# floppyswitch_4layer_smd.net
KiCad netlist of a schematic drawn in EAGLE
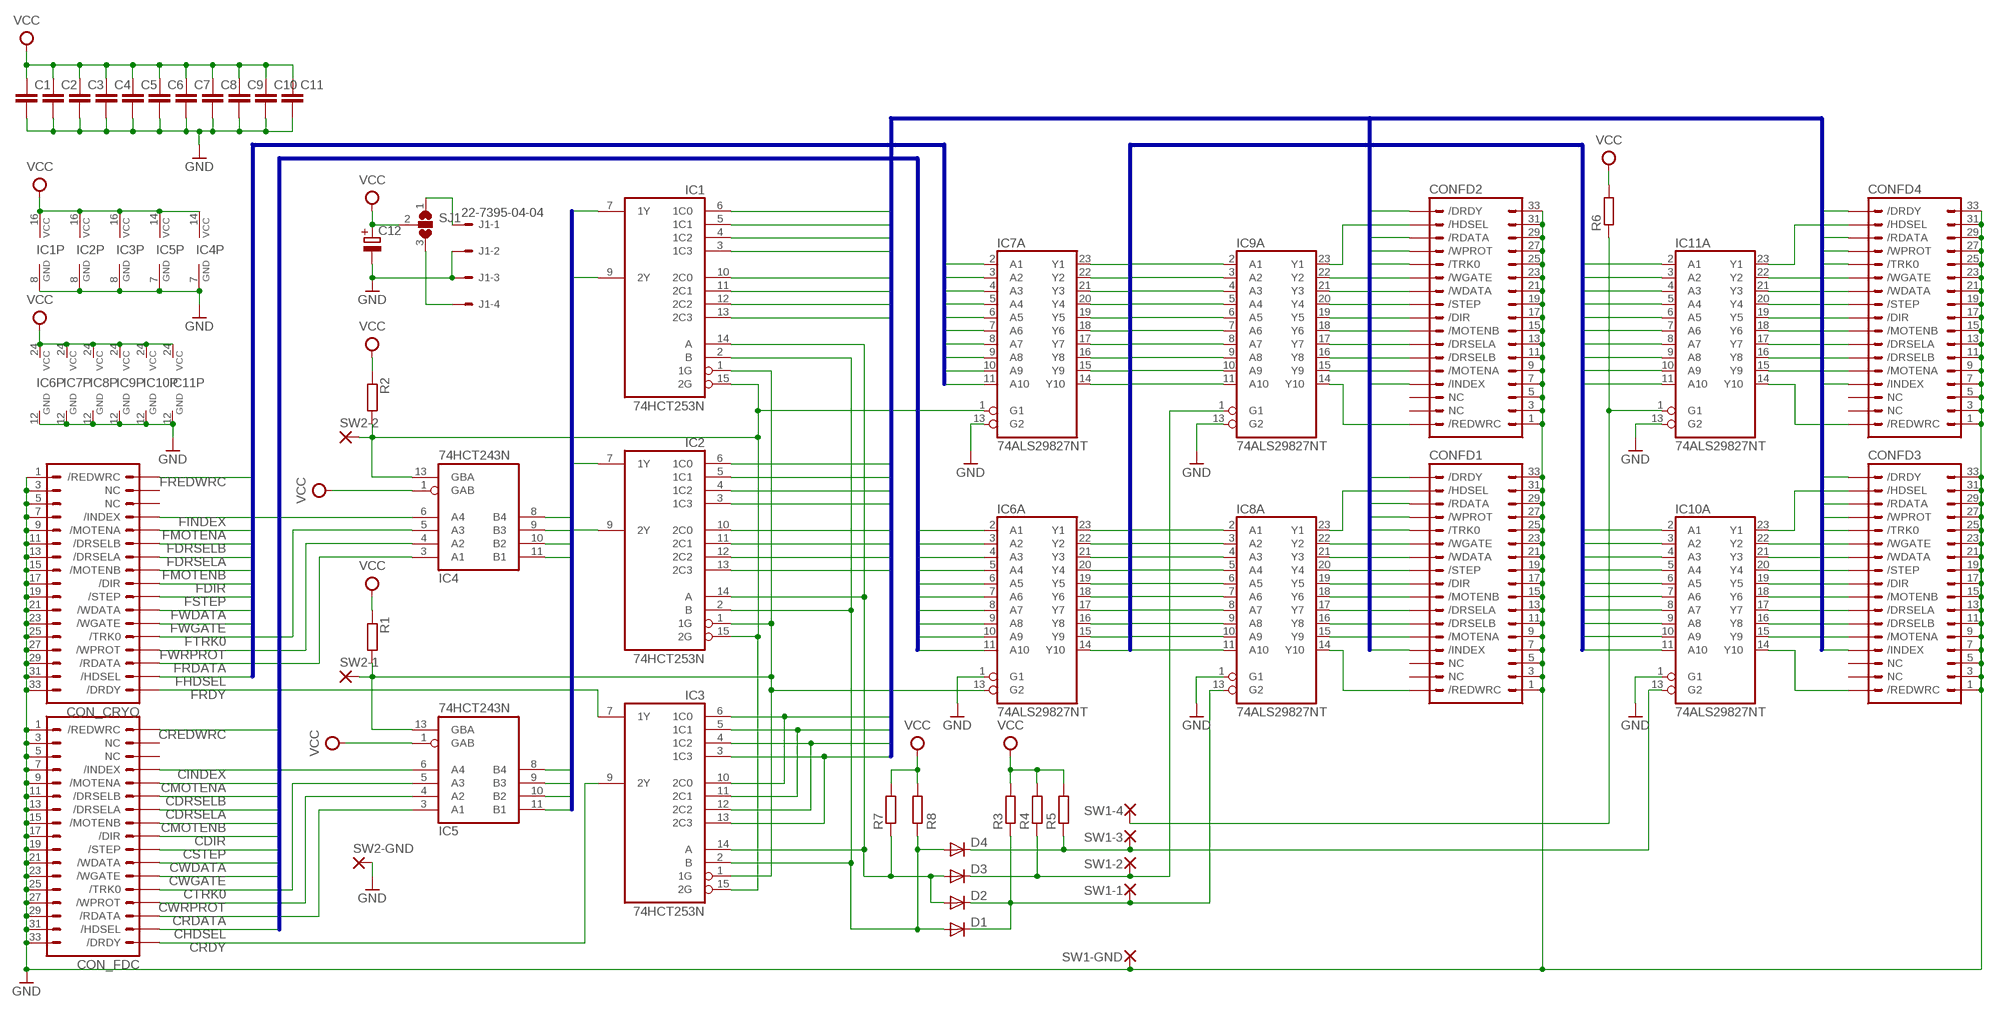
[diagram p0: schematic, sheet 1]

(export (version "E")
  (design (tool "Eeschema 10.0.6"))
  (components
    (comp (ref "C1")
      (value "C-EU075-032X103")
      (footprint "eagle-import:C075-032X103")
      (libsource (lib "eagle-import") (part "C-EU075-032X103"))
    )
    (comp (ref "C2")
      (value "C-EU025-025X050")
      (footprint "eagle-import:C025-025X050")
      (libsource (lib "eagle-import") (part "C-EU025-025X050"))
    )
    (comp (ref "C3")
      (value "C-EU050-025X075")
      (footprint "eagle-import:C050-025X075")
      (libsource (lib "eagle-import") (part "C-EU050-025X075"))
    )
    (comp (ref "C4")
      (value "C-EU050-025X075")
      (footprint "eagle-import:C050-025X075")
      (libsource (lib "eagle-import") (part "C-EU050-025X075"))
    )
    (comp (ref "C5")
      (value "C-EU075-032X103")
      (footprint "eagle-import:C075-032X103")
      (libsource (lib "eagle-import") (part "C-EU075-032X103"))
    )
    (comp (ref "C6")
      (value "C-EU075-032X103")
      (footprint "eagle-import:C075-032X103")
      (libsource (lib "eagle-import") (part "C-EU075-032X103"))
    )
    (comp (ref "C7")
      (value "C-EU075-032X103")
      (footprint "eagle-import:C075-032X103")
      (libsource (lib "eagle-import") (part "C-EU075-032X103"))
    )
    (comp (ref "C8")
      (value "C-EU075-032X103")
      (footprint "eagle-import:C075-032X103")
      (libsource (lib "eagle-import") (part "C-EU075-032X103"))
    )
    (comp (ref "C9")
      (value "C-EU075-032X103")
      (footprint "eagle-import:C075-032X103")
      (libsource (lib "eagle-import") (part "C-EU075-032X103"))
    )
    (comp (ref "C10")
      (value "C-EU075-032X103")
      (footprint "eagle-import:C075-032X103")
      (libsource (lib "eagle-import") (part "C-EU075-032X103"))
    )
    (comp (ref "C11")
      (value "C-EU050-025X075")
      (footprint "eagle-import:C050-025X075")
      (libsource (lib "eagle-import") (part "C-EU050-025X075"))
    )
    (comp (ref "C12")
      (value "CPOL-EUE2.5-6")
      (footprint "eagle-import:E2,5-6")
      (libsource (lib "eagle-import") (part "CPOL-EUE2.5-6"))
    )
    (comp (ref "CONFD1")
      (value "FDC342X17")
      (footprint "eagle-import:2X17")
      (libsource (lib "eagle-import") (part "FDC342X17"))
    )
    (comp (ref "CONFD2")
      (value "FDC342X17")
      (footprint "eagle-import:2X17")
      (libsource (lib "eagle-import") (part "FDC342X17"))
    )
    (comp (ref "CONFD3")
      (value "FDC342X17")
      (footprint "eagle-import:2X17")
      (libsource (lib "eagle-import") (part "FDC342X17"))
    )
    (comp (ref "CONFD4")
      (value "FDC342X17")
      (footprint "eagle-import:2X17")
      (libsource (lib "eagle-import") (part "FDC342X17"))
    )
    (comp (ref "CON_CRYO")
      (value "FDC342X17")
      (footprint "eagle-import:2X17")
      (libsource (lib "eagle-import") (part "FDC342X17"))
    )
    (comp (ref "CON_FDC")
      (value "FDC342X17")
      (footprint "eagle-import:2X17")
      (libsource (lib "eagle-import") (part "FDC342X17"))
    )
    (comp (ref "D1")
      (value "1N4148-7")
      (footprint "eagle-import:DO35-7")
      (libsource (lib "eagle-import") (part "1N4148-7"))
    )
    (comp (ref "D2")
      (value "1N4148-7")
      (footprint "eagle-import:DO35-7")
      (libsource (lib "eagle-import") (part "1N4148-7"))
    )
    (comp (ref "D3")
      (value "1N4148-7")
      (footprint "eagle-import:DO35-7")
      (libsource (lib "eagle-import") (part "1N4148-7"))
    )
    (comp (ref "D4")
      (value "1N4148-7")
      (footprint "eagle-import:DO35-7")
      (libsource (lib "eagle-import") (part "1N4148-7"))
    )
    (comp (ref "IC1")
      (value "74HCT253N")
      (footprint "eagle-import:DIL16")
      (libsource (lib "eagle-import") (part "74253NHCT"))
    )
    (comp (ref "IC2")
      (value "74HCT253N")
      (footprint "eagle-import:DIL16")
      (libsource (lib "eagle-import") (part "74253NHCT"))
    )
    (comp (ref "IC3")
      (value "74HCT253N")
      (footprint "eagle-import:DIL16")
      (libsource (lib "eagle-import") (part "74253NHCT"))
    )
    (comp (ref "IC4")
      (value "74HCT243N")
      (footprint "eagle-import:DIL14")
      (libsource (lib "eagle-import") (part "74243NHCT"))
    )
    (comp (ref "IC5")
      (value "74HCT243N")
      (footprint "eagle-import:DIL14")
      (libsource (lib "eagle-import") (part "74243NHCT"))
    )
    (comp (ref "IC6")
      (value "74ALS29827NT")
      (footprint "eagle-import:SO24W")
      (libsource (lib "eagle-import") (part "7429827NTALS"))
    )
    (comp (ref "IC7")
      (value "74ALS29827NT")
      (footprint "eagle-import:SO24W")
      (libsource (lib "eagle-import") (part "7429827NTALS"))
    )
    (comp (ref "IC8")
      (value "74ALS29827NT")
      (footprint "eagle-import:SO24W")
      (libsource (lib "eagle-import") (part "7429827NTALS"))
    )
    (comp (ref "IC9")
      (value "74ALS29827NT")
      (footprint "eagle-import:SO24W")
      (libsource (lib "eagle-import") (part "7429827NTALS"))
    )
    (comp (ref "IC10")
      (value "74ALS29827NT")
      (footprint "eagle-import:SO24W")
      (libsource (lib "eagle-import") (part "7429827NTALS"))
    )
    (comp (ref "IC11")
      (value "74ALS29827NT")
      (footprint "eagle-import:SO24W")
      (libsource (lib "eagle-import") (part "7429827NTALS"))
    )
    (comp (ref "J1")
      (value "22-7395-04-04")
      (footprint "eagle-import:7395-04")
      (libsource (lib "eagle-import") (part "22-?-047395-04"))
    )
    (comp (ref "R1")
      (value "R-EU0207/10")
      (footprint "eagle-import:0207_10")
      (libsource (lib "eagle-import") (part "R-EU0207/10"))
    )
    (comp (ref "R2")
      (value "R-EU0207/10")
      (footprint "eagle-import:0207_10")
      (libsource (lib "eagle-import") (part "R-EU0207/10"))
    )
    (comp (ref "R3")
      (value "R-EU0207/10")
      (footprint "eagle-import:0207_10")
      (libsource (lib "eagle-import") (part "R-EU0207/10"))
    )
    (comp (ref "R4")
      (value "R-EU0207/10")
      (footprint "eagle-import:0207_10")
      (libsource (lib "eagle-import") (part "R-EU0207/10"))
    )
    (comp (ref "R5")
      (value "R-EU0207/10")
      (footprint "eagle-import:0207_10")
      (libsource (lib "eagle-import") (part "R-EU0207/10"))
    )
    (comp (ref "R6")
      (value "R-EU0207/10")
      (footprint "eagle-import:0207_10")
      (libsource (lib "eagle-import") (part "R-EU0207/10"))
    )
    (comp (ref "R7")
      (value "R-EU0207/10")
      (footprint "eagle-import:0207_10")
      (libsource (lib "eagle-import") (part "R-EU0207/10"))
    )
    (comp (ref "R8")
      (value "R-EU0207/10")
      (footprint "eagle-import:0207_10")
      (libsource (lib "eagle-import") (part "R-EU0207/10"))
    )
    (comp (ref "SJ1")
      (value "SJ2W")
      (footprint "eagle-import:SJ_2")
      (libsource (lib "eagle-import") (part "SJ2W"))
    )
    (comp (ref "SW1-1")
      (value "WIREPAD1,6/0,8")
      (footprint "eagle-import:1,6_0,8")
      (libsource (lib "eagle-import") (part "WIREPAD1,6/0,8"))
    )
    (comp (ref "SW1-2")
      (value "WIREPAD1,6/0,8")
      (footprint "eagle-import:1,6_0,8")
      (libsource (lib "eagle-import") (part "WIREPAD1,6/0,8"))
    )
    (comp (ref "SW1-3")
      (value "WIREPAD1,6/0,8")
      (footprint "eagle-import:1,6_0,8")
      (libsource (lib "eagle-import") (part "WIREPAD1,6/0,8"))
    )
    (comp (ref "SW1-4")
      (value "WIREPAD1,6/0,8")
      (footprint "eagle-import:1,6_0,8")
      (libsource (lib "eagle-import") (part "WIREPAD1,6/0,8"))
    )
    (comp (ref "SW1-GND")
      (value "WIREPAD1,6/0,8")
      (footprint "eagle-import:1,6_0,8")
      (libsource (lib "eagle-import") (part "WIREPAD1,6/0,8"))
    )
    (comp (ref "SW2-1")
      (value "WIREPAD1,6/0,8")
      (footprint "eagle-import:1,6_0,8")
      (libsource (lib "eagle-import") (part "WIREPAD1,6/0,8"))
    )
    (comp (ref "SW2-2")
      (value "WIREPAD1,6/0,8")
      (footprint "eagle-import:1,6_0,8")
      (libsource (lib "eagle-import") (part "WIREPAD1,6/0,8"))
    )
    (comp (ref "SW2-GND")
      (value "WIREPAD1,6/0,8")
      (footprint "eagle-import:1,6_0,8")
      (libsource (lib "eagle-import") (part "WIREPAD1,6/0,8"))
    )
  )
  (nets
    (net (code "1") (name "/BUS1") (class "Default")
      (node (ref "IC10") (pin "11") (pinfunction "A10_11") (pintype "input"))
      (node (ref "IC11") (pin "11") (pinfunction "A10_11") (pintype "input"))
      (node (ref "IC6") (pin "14") (pinfunction "Y10_14") (pintype "tri_state"))
      (node (ref "IC7") (pin "14") (pinfunction "Y10_14") (pintype "tri_state"))
      (node (ref "IC8") (pin "11") (pinfunction "A10_11") (pintype "input"))
      (node (ref "IC9") (pin "11") (pinfunction "A10_11") (pintype "input"))
    )
    (net (code "2") (name "/BUS2") (class "Default")
      (node (ref "IC10") (pin "10") (pinfunction "A9_10") (pintype "input"))
      (node (ref "IC11") (pin "10") (pinfunction "A9_10") (pintype "input"))
      (node (ref "IC6") (pin "15") (pinfunction "Y9_15") (pintype "tri_state"))
      (node (ref "IC7") (pin "15") (pinfunction "Y9_15") (pintype "tri_state"))
      (node (ref "IC8") (pin "10") (pinfunction "A9_10") (pintype "input"))
      (node (ref "IC9") (pin "10") (pinfunction "A9_10") (pintype "input"))
    )
    (net (code "3") (name "/BUS3") (class "Default")
      (node (ref "IC10") (pin "9") (pinfunction "A8_9") (pintype "input"))
      (node (ref "IC11") (pin "9") (pinfunction "A8_9") (pintype "input"))
      (node (ref "IC6") (pin "16") (pinfunction "Y8_16") (pintype "tri_state"))
      (node (ref "IC7") (pin "16") (pinfunction "Y8_16") (pintype "tri_state"))
      (node (ref "IC8") (pin "9") (pinfunction "A8_9") (pintype "input"))
      (node (ref "IC9") (pin "9") (pinfunction "A8_9") (pintype "input"))
    )
    (net (code "4") (name "/BUS4") (class "Default")
      (node (ref "IC10") (pin "8") (pinfunction "A7_8") (pintype "input"))
      (node (ref "IC11") (pin "8") (pinfunction "A7_8") (pintype "input"))
      (node (ref "IC6") (pin "17") (pinfunction "Y7_17") (pintype "tri_state"))
      (node (ref "IC7") (pin "17") (pinfunction "Y7_17") (pintype "tri_state"))
      (node (ref "IC8") (pin "8") (pinfunction "A7_8") (pintype "input"))
      (node (ref "IC9") (pin "8") (pinfunction "A7_8") (pintype "input"))
    )
    (net (code "5") (name "/BUS5") (class "Default")
      (node (ref "IC10") (pin "7") (pinfunction "A6_7") (pintype "input"))
      (node (ref "IC11") (pin "7") (pinfunction "A6_7") (pintype "input"))
      (node (ref "IC6") (pin "18") (pinfunction "Y6_18") (pintype "tri_state"))
      (node (ref "IC7") (pin "18") (pinfunction "Y6_18") (pintype "tri_state"))
      (node (ref "IC8") (pin "7") (pinfunction "A6_7") (pintype "input"))
      (node (ref "IC9") (pin "7") (pinfunction "A6_7") (pintype "input"))
    )
    (net (code "6") (name "/BUS6") (class "Default")
      (node (ref "IC10") (pin "6") (pinfunction "A5_6") (pintype "input"))
      (node (ref "IC11") (pin "6") (pinfunction "A5_6") (pintype "input"))
      (node (ref "IC6") (pin "19") (pinfunction "Y5_19") (pintype "tri_state"))
      (node (ref "IC7") (pin "19") (pinfunction "Y5_19") (pintype "tri_state"))
      (node (ref "IC8") (pin "6") (pinfunction "A5_6") (pintype "input"))
      (node (ref "IC9") (pin "6") (pinfunction "A5_6") (pintype "input"))
    )
    (net (code "7") (name "/BUS7") (class "Default")
      (node (ref "IC10") (pin "5") (pinfunction "A4_5") (pintype "input"))
      (node (ref "IC11") (pin "5") (pinfunction "A4_5") (pintype "input"))
      (node (ref "IC6") (pin "20") (pinfunction "Y4_20") (pintype "tri_state"))
      (node (ref "IC7") (pin "20") (pinfunction "Y4_20") (pintype "tri_state"))
      (node (ref "IC8") (pin "5") (pinfunction "A4_5") (pintype "input"))
      (node (ref "IC9") (pin "5") (pinfunction "A4_5") (pintype "input"))
    )
    (net (code "8") (name "/BUS8") (class "Default")
      (node (ref "IC10") (pin "4") (pinfunction "A3_4") (pintype "input"))
      (node (ref "IC11") (pin "4") (pinfunction "A3_4") (pintype "input"))
      (node (ref "IC6") (pin "21") (pinfunction "Y3_21") (pintype "tri_state"))
      (node (ref "IC7") (pin "21") (pinfunction "Y3_21") (pintype "tri_state"))
      (node (ref "IC8") (pin "4") (pinfunction "A3_4") (pintype "input"))
      (node (ref "IC9") (pin "4") (pinfunction "A3_4") (pintype "input"))
    )
    (net (code "9") (name "/BUS9") (class "Default")
      (node (ref "IC10") (pin "3") (pinfunction "A2_3") (pintype "input"))
      (node (ref "IC11") (pin "3") (pinfunction "A2_3") (pintype "input"))
      (node (ref "IC6") (pin "22") (pinfunction "Y2_22") (pintype "tri_state"))
      (node (ref "IC7") (pin "22") (pinfunction "Y2_22") (pintype "tri_state"))
      (node (ref "IC8") (pin "3") (pinfunction "A2_3") (pintype "input"))
      (node (ref "IC9") (pin "3") (pinfunction "A2_3") (pintype "input"))
    )
    (net (code "10") (name "/BUS10") (class "Default")
      (node (ref "IC10") (pin "2") (pinfunction "A1_2") (pintype "input"))
      (node (ref "IC11") (pin "2") (pinfunction "A1_2") (pintype "input"))
      (node (ref "IC6") (pin "23") (pinfunction "Y1_23") (pintype "tri_state"))
      (node (ref "IC7") (pin "23") (pinfunction "Y1_23") (pintype "tri_state"))
      (node (ref "IC8") (pin "2") (pinfunction "A1_2") (pintype "input"))
      (node (ref "IC9") (pin "2") (pinfunction "A1_2") (pintype "input"))
    )
    (net (code "11") (name "/CDIR") (class "Default")
      (node (ref "CON_FDC") (pin "18") (pinfunction "/DIR_18") (pintype "output"))
      (node (ref "IC6") (pin "6") (pinfunction "A5_6") (pintype "input"))
    )
    (net (code "12") (name "/CDRSELA") (class "Default")
      (node (ref "CON_FDC") (pin "14") (pinfunction "/DRSELA_14") (pintype "output"))
      (node (ref "IC6") (pin "8") (pinfunction "A7_8") (pintype "input"))
    )
    (net (code "13") (name "/CDRSELB") (class "Default")
      (node (ref "CON_FDC") (pin "12") (pinfunction "/DRSELB_12") (pintype "output"))
      (node (ref "IC6") (pin "9") (pinfunction "A8_9") (pintype "input"))
    )
    (net (code "14") (name "/CHDSEL") (class "Default")
      (node (ref "CON_FDC") (pin "32") (pinfunction "/HDSEL_32") (pintype "output"))
      (node (ref "IC6") (pin "2") (pinfunction "A1_2") (pintype "input"))
    )
    (net (code "15") (name "/CINDEX") (class "Default")
      (node (ref "CON_FDC") (pin "8") (pinfunction "/INDEX_8") (pintype "input"))
      (node (ref "IC5") (pin "6") (pinfunction "A4_6") (pintype "bidirectional"))
    )
    (net (code "16") (name "/CMOTENA") (class "Default")
      (node (ref "CON_FDC") (pin "10") (pinfunction "/MOTENA_10") (pintype "output"))
      (node (ref "IC6") (pin "10") (pinfunction "A9_10") (pintype "input"))
    )
    (net (code "17") (name "/CMOTENB") (class "Default")
      (node (ref "CON_FDC") (pin "16") (pinfunction "/MOTENB_16") (pintype "output"))
      (node (ref "IC6") (pin "7") (pinfunction "A6_7") (pintype "input"))
    )
    (net (code "18") (name "/CRDATA") (class "Default")
      (node (ref "CON_FDC") (pin "30") (pinfunction "/RDATA_30") (pintype "input"))
      (node (ref "IC5") (pin "3") (pinfunction "A1_3") (pintype "bidirectional"))
    )
    (net (code "19") (name "/CRDY") (class "Default")
      (node (ref "CON_FDC") (pin "34") (pinfunction "/DRDY_34") (pintype "input"))
      (node (ref "IC3") (pin "9") (pinfunction "2Y_9") (pintype "tri_state"))
    )
    (net (code "20") (name "/CREDWRC") (class "Default")
      (node (ref "CON_FDC") (pin "2") (pinfunction "/REDWRC_2") (pintype "output"))
      (node (ref "IC6") (pin "11") (pinfunction "A10_11") (pintype "input"))
    )
    (net (code "21") (name "/CSTEP") (class "Default")
      (node (ref "CON_FDC") (pin "20") (pinfunction "/STEP_20") (pintype "output"))
      (node (ref "IC6") (pin "5") (pinfunction "A4_5") (pintype "input"))
    )
    (net (code "22") (name "/CTRK0") (class "Default")
      (node (ref "CON_FDC") (pin "26") (pinfunction "/TRK0_26") (pintype "input"))
      (node (ref "IC5") (pin "5") (pinfunction "A3_5") (pintype "bidirectional"))
    )
    (net (code "23") (name "/CWDATA") (class "Default")
      (node (ref "CON_FDC") (pin "22") (pinfunction "/WDATA_22") (pintype "output"))
      (node (ref "IC6") (pin "4") (pinfunction "A3_4") (pintype "input"))
    )
    (net (code "24") (name "/CWGATE") (class "Default")
      (node (ref "CON_FDC") (pin "24") (pinfunction "/WGATE_24") (pintype "output"))
      (node (ref "IC6") (pin "3") (pinfunction "A2_3") (pintype "input"))
    )
    (net (code "25") (name "/CWRPROT") (class "Default")
      (node (ref "CON_FDC") (pin "28") (pinfunction "/WPROT_28") (pintype "input"))
      (node (ref "IC5") (pin "4") (pinfunction "A2_4") (pintype "bidirectional"))
    )
    (net (code "26") (name "/FDIR") (class "Default")
      (node (ref "CON_CRYO") (pin "18") (pinfunction "/DIR_18") (pintype "output"))
      (node (ref "IC7") (pin "6") (pinfunction "A5_6") (pintype "input"))
    )
    (net (code "27") (name "/FDRSELA") (class "Default")
      (node (ref "CON_CRYO") (pin "14") (pinfunction "/DRSELA_14") (pintype "output"))
      (node (ref "IC7") (pin "8") (pinfunction "A7_8") (pintype "input"))
    )
    (net (code "28") (name "/FDRSELB") (class "Default")
      (node (ref "CON_CRYO") (pin "12") (pinfunction "/DRSELB_12") (pintype "output"))
      (node (ref "IC7") (pin "9") (pinfunction "A8_9") (pintype "input"))
    )
    (net (code "29") (name "/FHDSEL") (class "Default")
      (node (ref "CON_CRYO") (pin "32") (pinfunction "/HDSEL_32") (pintype "output"))
      (node (ref "IC7") (pin "2") (pinfunction "A1_2") (pintype "input"))
    )
    (net (code "30") (name "/FINDEX") (class "Default")
      (node (ref "CON_CRYO") (pin "8") (pinfunction "/INDEX_8") (pintype "input"))
      (node (ref "IC4") (pin "6") (pinfunction "A4_6") (pintype "bidirectional"))
    )
    (net (code "31") (name "/FMOTENA") (class "Default")
      (node (ref "CON_CRYO") (pin "10") (pinfunction "/MOTENA_10") (pintype "output"))
      (node (ref "IC7") (pin "10") (pinfunction "A9_10") (pintype "input"))
    )
    (net (code "32") (name "/FMOTENB") (class "Default")
      (node (ref "CON_CRYO") (pin "16") (pinfunction "/MOTENB_16") (pintype "output"))
      (node (ref "IC7") (pin "7") (pinfunction "A6_7") (pintype "input"))
    )
    (net (code "33") (name "/FRDATA") (class "Default")
      (node (ref "CON_CRYO") (pin "30") (pinfunction "/RDATA_30") (pintype "input"))
      (node (ref "IC4") (pin "3") (pinfunction "A1_3") (pintype "bidirectional"))
    )
    (net (code "34") (name "/FRDY") (class "Default")
      (node (ref "CON_CRYO") (pin "34") (pinfunction "/DRDY_34") (pintype "input"))
      (node (ref "IC3") (pin "7") (pinfunction "1Y_7") (pintype "tri_state"))
    )
    (net (code "35") (name "/FREDWRC") (class "Default")
      (node (ref "CON_CRYO") (pin "2") (pinfunction "/REDWRC_2") (pintype "output"))
      (node (ref "IC7") (pin "11") (pinfunction "A10_11") (pintype "input"))
    )
    (net (code "36") (name "/FSTEP") (class "Default")
      (node (ref "CON_CRYO") (pin "20") (pinfunction "/STEP_20") (pintype "output"))
      (node (ref "IC7") (pin "5") (pinfunction "A4_5") (pintype "input"))
    )
    (net (code "37") (name "/FTRK0") (class "Default")
      (node (ref "CON_CRYO") (pin "26") (pinfunction "/TRK0_26") (pintype "input"))
      (node (ref "IC4") (pin "5") (pinfunction "A3_5") (pintype "bidirectional"))
    )
    (net (code "38") (name "/FWDATA") (class "Default")
      (node (ref "CON_CRYO") (pin "22") (pinfunction "/WDATA_22") (pintype "output"))
      (node (ref "IC7") (pin "4") (pinfunction "A3_4") (pintype "input"))
    )
    (net (code "39") (name "/FWGATE") (class "Default")
      (node (ref "CON_CRYO") (pin "24") (pinfunction "/WGATE_24") (pintype "output"))
      (node (ref "IC7") (pin "3") (pinfunction "A2_3") (pintype "input"))
    )
    (net (code "40") (name "/FWRPROT") (class "Default")
      (node (ref "CON_CRYO") (pin "28") (pinfunction "/WPROT_28") (pintype "input"))
      (node (ref "IC4") (pin "4") (pinfunction "A2_4") (pintype "bidirectional"))
    )
    (net (code "41") (name "/INDEX") (class "Default")
      (node (ref "IC1") (pin "7") (pinfunction "1Y_7") (pintype "tri_state"))
      (node (ref "IC4") (pin "8") (pinfunction "B4_8") (pintype "bidirectional"))
      (node (ref "IC5") (pin "8") (pinfunction "B4_8") (pintype "bidirectional"))
    )
    (net (code "42") (name "/INDEX1") (class "Default")
      (node (ref "CONFD1") (pin "8") (pinfunction "/INDEX_8") (pintype "input"))
      (node (ref "IC1") (pin "6") (pinfunction "1C0_6") (pintype "input"))
    )
    (net (code "43") (name "/INDEX2") (class "Default")
      (node (ref "CONFD2") (pin "8") (pinfunction "/INDEX_8") (pintype "input"))
      (node (ref "IC1") (pin "5") (pinfunction "1C1_5") (pintype "input"))
    )
    (net (code "44") (name "/INDEX3") (class "Default")
      (node (ref "CONFD3") (pin "8") (pinfunction "/INDEX_8") (pintype "input"))
      (node (ref "IC1") (pin "4") (pinfunction "1C2_4") (pintype "input"))
    )
    (net (code "45") (name "/INDEX4") (class "Default")
      (node (ref "CONFD4") (pin "8") (pinfunction "/INDEX_8") (pintype "input"))
      (node (ref "IC1") (pin "3") (pinfunction "1C3_3") (pintype "input"))
    )
    (net (code "46") (name "/RDATA") (class "Default")
      (node (ref "IC2") (pin "9") (pinfunction "2Y_9") (pintype "tri_state"))
      (node (ref "IC4") (pin "11") (pinfunction "B1_11") (pintype "bidirectional"))
      (node (ref "IC5") (pin "11") (pinfunction "B1_11") (pintype "bidirectional"))
    )
    (net (code "47") (name "/RDATA1") (class "Default")
      (node (ref "CONFD1") (pin "30") (pinfunction "/RDATA_30") (pintype "input"))
      (node (ref "IC2") (pin "10") (pinfunction "2C0_10") (pintype "input"))
    )
    (net (code "48") (name "/RDATA2") (class "Default")
      (node (ref "CONFD2") (pin "30") (pinfunction "/RDATA_30") (pintype "input"))
      (node (ref "IC2") (pin "11") (pinfunction "2C1_11") (pintype "input"))
    )
    (net (code "49") (name "/RDATA3") (class "Default")
      (node (ref "CONFD3") (pin "30") (pinfunction "/RDATA_30") (pintype "input"))
      (node (ref "IC2") (pin "12") (pinfunction "2C2_12") (pintype "input"))
    )
    (net (code "50") (name "/RDATA4") (class "Default")
      (node (ref "CONFD4") (pin "30") (pinfunction "/RDATA_30") (pintype "input"))
      (node (ref "IC2") (pin "13") (pinfunction "2C3_13") (pintype "input"))
    )
    (net (code "51") (name "/RDY1") (class "Default")
      (node (ref "CONFD1") (pin "34") (pinfunction "/DRDY_34") (pintype "input"))
      (node (ref "IC3") (pin "10") (pinfunction "2C0_10") (pintype "input"))
      (node (ref "IC3") (pin "6") (pinfunction "1C0_6") (pintype "input"))
    )
    (net (code "52") (name "/RDY2") (class "Default")
      (node (ref "CONFD2") (pin "34") (pinfunction "/DRDY_34") (pintype "input"))
      (node (ref "IC3") (pin "11") (pinfunction "2C1_11") (pintype "input"))
      (node (ref "IC3") (pin "5") (pinfunction "1C1_5") (pintype "input"))
    )
    (net (code "53") (name "/RDY3") (class "Default")
      (node (ref "CONFD3") (pin "34") (pinfunction "/DRDY_34") (pintype "input"))
      (node (ref "IC3") (pin "12") (pinfunction "2C2_12") (pintype "input"))
      (node (ref "IC3") (pin "4") (pinfunction "1C2_4") (pintype "input"))
    )
    (net (code "54") (name "/RDY4") (class "Default")
      (node (ref "CONFD4") (pin "34") (pinfunction "/DRDY_34") (pintype "input"))
      (node (ref "IC3") (pin "13") (pinfunction "2C3_13") (pintype "input"))
      (node (ref "IC3") (pin "3") (pinfunction "1C3_3") (pintype "input"))
    )
    (net (code "55") (name "/TRK0") (class "Default")
      (node (ref "IC1") (pin "9") (pinfunction "2Y_9") (pintype "tri_state"))
      (node (ref "IC4") (pin "9") (pinfunction "B3_9") (pintype "bidirectional"))
      (node (ref "IC5") (pin "9") (pinfunction "B3_9") (pintype "bidirectional"))
    )
    (net (code "56") (name "/TRKZ1") (class "Default")
      (node (ref "CONFD1") (pin "26") (pinfunction "/TRK0_26") (pintype "input"))
      (node (ref "IC1") (pin "10") (pinfunction "2C0_10") (pintype "input"))
    )
    (net (code "57") (name "/TRKZ2") (class "Default")
      (node (ref "CONFD2") (pin "26") (pinfunction "/TRK0_26") (pintype "input"))
      (node (ref "IC1") (pin "11") (pinfunction "2C1_11") (pintype "input"))
    )
    (net (code "58") (name "/TRKZ3") (class "Default")
      (node (ref "CONFD3") (pin "26") (pinfunction "/TRK0_26") (pintype "input"))
      (node (ref "IC1") (pin "12") (pinfunction "2C2_12") (pintype "input"))
    )
    (net (code "59") (name "/TRKZ4") (class "Default")
      (node (ref "CONFD4") (pin "26") (pinfunction "/TRK0_26") (pintype "input"))
      (node (ref "IC1") (pin "13") (pinfunction "2C3_13") (pintype "input"))
    )
    (net (code "60") (name "/WRPROT") (class "Default")
      (node (ref "IC2") (pin "7") (pinfunction "1Y_7") (pintype "tri_state"))
      (node (ref "IC4") (pin "10") (pinfunction "B2_10") (pintype "bidirectional"))
      (node (ref "IC5") (pin "10") (pinfunction "B2_10") (pintype "bidirectional"))
    )
    (net (code "61") (name "/WRPROT1") (class "Default")
      (node (ref "CONFD1") (pin "28") (pinfunction "/WPROT_28") (pintype "input"))
      (node (ref "IC2") (pin "6") (pinfunction "1C0_6") (pintype "input"))
    )
    (net (code "62") (name "/WRPROT2") (class "Default")
      (node (ref "CONFD2") (pin "28") (pinfunction "/WPROT_28") (pintype "input"))
      (node (ref "IC2") (pin "5") (pinfunction "1C1_5") (pintype "input"))
    )
    (net (code "63") (name "/WRPROT3") (class "Default")
      (node (ref "CONFD3") (pin "28") (pinfunction "/WPROT_28") (pintype "input"))
      (node (ref "IC2") (pin "4") (pinfunction "1C2_4") (pintype "input"))
    )
    (net (code "64") (name "/WRPROT4") (class "Default")
      (node (ref "CONFD4") (pin "28") (pinfunction "/WPROT_28") (pintype "input"))
      (node (ref "IC2") (pin "3") (pinfunction "1C3_3") (pintype "input"))
    )
    (net (code "65") (name "GND") (class "Default")
      (node (ref "C1") (pin "2") (pinfunction "2_2") (pintype "passive"))
      (node (ref "C10") (pin "2") (pinfunction "2_2") (pintype "passive"))
      (node (ref "C11") (pin "2") (pinfunction "2_2") (pintype "passive"))
      (node (ref "C12") (pin "-") (pinfunction "-_-") (pintype "passive"))
      (node (ref "C2") (pin "2") (pinfunction "2_2") (pintype "passive"))
      (node (ref "C3") (pin "2") (pinfunction "2_2") (pintype "passive"))
      (node (ref "C4") (pin "2") (pinfunction "2_2") (pintype "passive"))
      (node (ref "C5") (pin "2") (pinfunction "2_2") (pintype "passive"))
      (node (ref "C6") (pin "2") (pinfunction "2_2") (pintype "passive"))
      (node (ref "C7") (pin "2") (pinfunction "2_2") (pintype "passive"))
      (node (ref "C8") (pin "2") (pinfunction "2_2") (pintype "passive"))
      (node (ref "C9") (pin "2") (pinfunction "2_2") (pintype "passive"))
      (node (ref "CONFD1") (pin "1") (pinfunction "1_1") (pintype "power_in"))
      (node (ref "CONFD1") (pin "11") (pinfunction "11_11") (pintype "power_in"))
      (node (ref "CONFD1") (pin "13") (pinfunction "13_13") (pintype "power_in"))
      (node (ref "CONFD1") (pin "15") (pinfunction "15_15") (pintype "power_in"))
      (node (ref "CONFD1") (pin "17") (pinfunction "17_17") (pintype "power_in"))
      (node (ref "CONFD1") (pin "19") (pinfunction "19_19") (pintype "power_in"))
      (node (ref "CONFD1") (pin "21") (pinfunction "21_21") (pintype "power_in"))
      (node (ref "CONFD1") (pin "23") (pinfunction "23_23") (pintype "power_in"))
      (node (ref "CONFD1") (pin "25") (pinfunction "25_25") (pintype "power_in"))
      (node (ref "CONFD1") (pin "27") (pinfunction "27_27") (pintype "power_in"))
      (node (ref "CONFD1") (pin "29") (pinfunction "29_29") (pintype "power_in"))
      (node (ref "CONFD1") (pin "3") (pinfunction "3_3") (pintype "power_in"))
      (node (ref "CONFD1") (pin "31") (pinfunction "31_31") (pintype "power_in"))
      (node (ref "CONFD1") (pin "33") (pinfunction "33_33") (pintype "power_in"))
      (node (ref "CONFD1") (pin "5") (pinfunction "5_5") (pintype "power_in"))
      (node (ref "CONFD1") (pin "7") (pinfunction "7_7") (pintype "power_in"))
      (node (ref "CONFD1") (pin "9") (pinfunction "9_9") (pintype "power_in"))
      (node (ref "CONFD2") (pin "1") (pinfunction "1_1") (pintype "power_in"))
      (node (ref "CONFD2") (pin "11") (pinfunction "11_11") (pintype "power_in"))
      (node (ref "CONFD2") (pin "13") (pinfunction "13_13") (pintype "power_in"))
      (node (ref "CONFD2") (pin "15") (pinfunction "15_15") (pintype "power_in"))
      (node (ref "CONFD2") (pin "17") (pinfunction "17_17") (pintype "power_in"))
      (node (ref "CONFD2") (pin "19") (pinfunction "19_19") (pintype "power_in"))
      (node (ref "CONFD2") (pin "21") (pinfunction "21_21") (pintype "power_in"))
      (node (ref "CONFD2") (pin "23") (pinfunction "23_23") (pintype "power_in"))
      (node (ref "CONFD2") (pin "25") (pinfunction "25_25") (pintype "power_in"))
      (node (ref "CONFD2") (pin "27") (pinfunction "27_27") (pintype "power_in"))
      (node (ref "CONFD2") (pin "29") (pinfunction "29_29") (pintype "power_in"))
      (node (ref "CONFD2") (pin "3") (pinfunction "3_3") (pintype "power_in"))
      (node (ref "CONFD2") (pin "31") (pinfunction "31_31") (pintype "power_in"))
      (node (ref "CONFD2") (pin "33") (pinfunction "33_33") (pintype "power_in"))
      (node (ref "CONFD2") (pin "5") (pinfunction "5_5") (pintype "power_in"))
      (node (ref "CONFD2") (pin "7") (pinfunction "7_7") (pintype "power_in"))
      (node (ref "CONFD2") (pin "9") (pinfunction "9_9") (pintype "power_in"))
      (node (ref "CONFD3") (pin "1") (pinfunction "1_1") (pintype "power_in"))
      (node (ref "CONFD3") (pin "11") (pinfunction "11_11") (pintype "power_in"))
      (node (ref "CONFD3") (pin "13") (pinfunction "13_13") (pintype "power_in"))
      (node (ref "CONFD3") (pin "15") (pinfunction "15_15") (pintype "power_in"))
      (node (ref "CONFD3") (pin "17") (pinfunction "17_17") (pintype "power_in"))
      (node (ref "CONFD3") (pin "19") (pinfunction "19_19") (pintype "power_in"))
      (node (ref "CONFD3") (pin "21") (pinfunction "21_21") (pintype "power_in"))
      (node (ref "CONFD3") (pin "23") (pinfunction "23_23") (pintype "power_in"))
      (node (ref "CONFD3") (pin "25") (pinfunction "25_25") (pintype "power_in"))
      (node (ref "CONFD3") (pin "27") (pinfunction "27_27") (pintype "power_in"))
      (node (ref "CONFD3") (pin "29") (pinfunction "29_29") (pintype "power_in"))
      (node (ref "CONFD3") (pin "3") (pinfunction "3_3") (pintype "power_in"))
      (node (ref "CONFD3") (pin "31") (pinfunction "31_31") (pintype "power_in"))
      (node (ref "CONFD3") (pin "33") (pinfunction "33_33") (pintype "power_in"))
      (node (ref "CONFD3") (pin "5") (pinfunction "5_5") (pintype "power_in"))
      (node (ref "CONFD3") (pin "7") (pinfunction "7_7") (pintype "power_in"))
      (node (ref "CONFD3") (pin "9") (pinfunction "9_9") (pintype "power_in"))
      (node (ref "CONFD4") (pin "1") (pinfunction "1_1") (pintype "power_in"))
      (node (ref "CONFD4") (pin "11") (pinfunction "11_11") (pintype "power_in"))
      (node (ref "CONFD4") (pin "13") (pinfunction "13_13") (pintype "power_in"))
      (node (ref "CONFD4") (pin "15") (pinfunction "15_15") (pintype "power_in"))
      (node (ref "CONFD4") (pin "17") (pinfunction "17_17") (pintype "power_in"))
      (node (ref "CONFD4") (pin "19") (pinfunction "19_19") (pintype "power_in"))
      (node (ref "CONFD4") (pin "21") (pinfunction "21_21") (pintype "power_in"))
      (node (ref "CONFD4") (pin "23") (pinfunction "23_23") (pintype "power_in"))
      (node (ref "CONFD4") (pin "25") (pinfunction "25_25") (pintype "power_in"))
      (node (ref "CONFD4") (pin "27") (pinfunction "27_27") (pintype "power_in"))
      (node (ref "CONFD4") (pin "29") (pinfunction "29_29") (pintype "power_in"))
      (node (ref "CONFD4") (pin "3") (pinfunction "3_3") (pintype "power_in"))
      (node (ref "CONFD4") (pin "31") (pinfunction "31_31") (pintype "power_in"))
      (node (ref "CONFD4") (pin "33") (pinfunction "33_33") (pintype "power_in"))
      (node (ref "CONFD4") (pin "5") (pinfunction "5_5") (pintype "power_in"))
      (node (ref "CONFD4") (pin "7") (pinfunction "7_7") (pintype "power_in"))
      (node (ref "CONFD4") (pin "9") (pinfunction "9_9") (pintype "power_in"))
      (node (ref "CON_CRYO") (pin "1") (pinfunction "1_1") (pintype "power_in"))
      (node (ref "CON_CRYO") (pin "11") (pinfunction "11_11") (pintype "power_in"))
      (node (ref "CON_CRYO") (pin "13") (pinfunction "13_13") (pintype "power_in"))
      (node (ref "CON_CRYO") (pin "15") (pinfunction "15_15") (pintype "power_in"))
      (node (ref "CON_CRYO") (pin "17") (pinfunction "17_17") (pintype "power_in"))
      (node (ref "CON_CRYO") (pin "19") (pinfunction "19_19") (pintype "power_in"))
      (node (ref "CON_CRYO") (pin "21") (pinfunction "21_21") (pintype "power_in"))
      (node (ref "CON_CRYO") (pin "23") (pinfunction "23_23") (pintype "power_in"))
      (node (ref "CON_CRYO") (pin "25") (pinfunction "25_25") (pintype "power_in"))
      (node (ref "CON_CRYO") (pin "27") (pinfunction "27_27") (pintype "power_in"))
      (node (ref "CON_CRYO") (pin "29") (pinfunction "29_29") (pintype "power_in"))
      (node (ref "CON_CRYO") (pin "3") (pinfunction "3_3") (pintype "power_in"))
      (node (ref "CON_CRYO") (pin "31") (pinfunction "31_31") (pintype "power_in"))
      (node (ref "CON_CRYO") (pin "33") (pinfunction "33_33") (pintype "power_in"))
      (node (ref "CON_CRYO") (pin "5") (pinfunction "5_5") (pintype "power_in"))
      (node (ref "CON_CRYO") (pin "7") (pinfunction "7_7") (pintype "power_in"))
      (node (ref "CON_CRYO") (pin "9") (pinfunction "9_9") (pintype "power_in"))
      (node (ref "CON_FDC") (pin "1") (pinfunction "1_1") (pintype "power_in"))
      (node (ref "CON_FDC") (pin "11") (pinfunction "11_11") (pintype "power_in"))
      (node (ref "CON_FDC") (pin "13") (pinfunction "13_13") (pintype "power_in"))
      (node (ref "CON_FDC") (pin "15") (pinfunction "15_15") (pintype "power_in"))
      (node (ref "CON_FDC") (pin "17") (pinfunction "17_17") (pintype "power_in"))
      (node (ref "CON_FDC") (pin "19") (pinfunction "19_19") (pintype "power_in"))
      (node (ref "CON_FDC") (pin "21") (pinfunction "21_21") (pintype "power_in"))
      (node (ref "CON_FDC") (pin "23") (pinfunction "23_23") (pintype "power_in"))
      (node (ref "CON_FDC") (pin "25") (pinfunction "25_25") (pintype "power_in"))
      (node (ref "CON_FDC") (pin "27") (pinfunction "27_27") (pintype "power_in"))
      (node (ref "CON_FDC") (pin "29") (pinfunction "29_29") (pintype "power_in"))
      (node (ref "CON_FDC") (pin "3") (pinfunction "3_3") (pintype "power_in"))
      (node (ref "CON_FDC") (pin "31") (pinfunction "31_31") (pintype "power_in"))
      (node (ref "CON_FDC") (pin "33") (pinfunction "33_33") (pintype "power_in"))
      (node (ref "CON_FDC") (pin "5") (pinfunction "5_5") (pintype "power_in"))
      (node (ref "CON_FDC") (pin "7") (pinfunction "7_7") (pintype "power_in"))
      (node (ref "CON_FDC") (pin "9") (pinfunction "9_9") (pintype "power_in"))
      (node (ref "IC1") (pin "8") (pinfunction "GND_8") (pintype "power_in"))
      (node (ref "IC10") (pin "1") (pinfunction "G1_1") (pintype "input"))
      (node (ref "IC10") (pin "12") (pinfunction "GND_12") (pintype "power_in"))
      (node (ref "IC11") (pin "12") (pinfunction "GND_12") (pintype "power_in"))
      (node (ref "IC11") (pin "13") (pinfunction "G2_13") (pintype "input"))
      (node (ref "IC2") (pin "8") (pinfunction "GND_8") (pintype "power_in"))
      (node (ref "IC3") (pin "8") (pinfunction "GND_8") (pintype "power_in"))
      (node (ref "IC4") (pin "7") (pinfunction "GND_7") (pintype "power_in"))
      (node (ref "IC5") (pin "7") (pinfunction "GND_7") (pintype "power_in"))
      (node (ref "IC6") (pin "1") (pinfunction "G1_1") (pintype "input"))
      (node (ref "IC6") (pin "12") (pinfunction "GND_12") (pintype "power_in"))
      (node (ref "IC7") (pin "12") (pinfunction "GND_12") (pintype "power_in"))
      (node (ref "IC7") (pin "13") (pinfunction "G2_13") (pintype "input"))
      (node (ref "IC8") (pin "1") (pinfunction "G1_1") (pintype "input"))
      (node (ref "IC8") (pin "12") (pinfunction "GND_12") (pintype "power_in"))
      (node (ref "IC9") (pin "12") (pinfunction "GND_12") (pintype "power_in"))
      (node (ref "IC9") (pin "13") (pinfunction "G2_13") (pintype "input"))
      (node (ref "J1") (pin "2") (pinfunction "S_2") (pintype "passive"))
      (node (ref "J1") (pin "3") (pinfunction "S_3") (pintype "passive"))
      (node (ref "SW1-GND") (pin "1") (pinfunction "P_1") (pintype "passive"))
      (node (ref "SW2-GND") (pin "1") (pinfunction "P_1") (pintype "passive"))
    )
    (net (code "66") (name "Net-(CONFD1-{slash}DIR)") (class "Default")
      (node (ref "CONFD1") (pin "18") (pinfunction "/DIR_18") (pintype "output"))
      (node (ref "IC8") (pin "19") (pinfunction "Y5_19") (pintype "tri_state"))
    )
    (net (code "67") (name "Net-(CONFD1-{slash}DRSELA)") (class "Default")
      (node (ref "CONFD1") (pin "14") (pinfunction "/DRSELA_14") (pintype "output"))
      (node (ref "IC8") (pin "17") (pinfunction "Y7_17") (pintype "tri_state"))
    )
    (net (code "68") (name "Net-(CONFD1-{slash}DRSELB)") (class "Default")
      (node (ref "CONFD1") (pin "12") (pinfunction "/DRSELB_12") (pintype "output"))
      (node (ref "IC8") (pin "16") (pinfunction "Y8_16") (pintype "tri_state"))
    )
    (net (code "69") (name "Net-(CONFD1-{slash}HDSEL)") (class "Default")
      (node (ref "CONFD1") (pin "32") (pinfunction "/HDSEL_32") (pintype "output"))
      (node (ref "IC8") (pin "23") (pinfunction "Y1_23") (pintype "tri_state"))
    )
    (net (code "70") (name "Net-(CONFD1-{slash}MOTENA)") (class "Default")
      (node (ref "CONFD1") (pin "10") (pinfunction "/MOTENA_10") (pintype "output"))
      (node (ref "IC8") (pin "15") (pinfunction "Y9_15") (pintype "tri_state"))
    )
    (net (code "71") (name "Net-(CONFD1-{slash}MOTENB)") (class "Default")
      (node (ref "CONFD1") (pin "16") (pinfunction "/MOTENB_16") (pintype "output"))
      (node (ref "IC8") (pin "18") (pinfunction "Y6_18") (pintype "tri_state"))
    )
    (net (code "72") (name "Net-(CONFD1-{slash}REDWRC)") (class "Default")
      (node (ref "CONFD1") (pin "2") (pinfunction "/REDWRC_2") (pintype "output"))
      (node (ref "IC8") (pin "14") (pinfunction "Y10_14") (pintype "tri_state"))
    )
    (net (code "73") (name "Net-(CONFD1-{slash}STEP)") (class "Default")
      (node (ref "CONFD1") (pin "20") (pinfunction "/STEP_20") (pintype "output"))
      (node (ref "IC8") (pin "20") (pinfunction "Y4_20") (pintype "tri_state"))
    )
    (net (code "74") (name "Net-(CONFD1-{slash}WDATA)") (class "Default")
      (node (ref "CONFD1") (pin "22") (pinfunction "/WDATA_22") (pintype "output"))
      (node (ref "IC8") (pin "21") (pinfunction "Y3_21") (pintype "tri_state"))
    )
    (net (code "75") (name "Net-(CONFD1-{slash}WGATE)") (class "Default")
      (node (ref "CONFD1") (pin "24") (pinfunction "/WGATE_24") (pintype "output"))
      (node (ref "IC8") (pin "22") (pinfunction "Y2_22") (pintype "tri_state"))
    )
    (net (code "76") (name "Net-(CONFD2-{slash}DIR)") (class "Default")
      (node (ref "CONFD2") (pin "18") (pinfunction "/DIR_18") (pintype "output"))
      (node (ref "IC9") (pin "19") (pinfunction "Y5_19") (pintype "tri_state"))
    )
    (net (code "77") (name "Net-(CONFD2-{slash}DRSELA)") (class "Default")
      (node (ref "CONFD2") (pin "14") (pinfunction "/DRSELA_14") (pintype "output"))
      (node (ref "IC9") (pin "17") (pinfunction "Y7_17") (pintype "tri_state"))
    )
    (net (code "78") (name "Net-(CONFD2-{slash}DRSELB)") (class "Default")
      (node (ref "CONFD2") (pin "12") (pinfunction "/DRSELB_12") (pintype "output"))
      (node (ref "IC9") (pin "16") (pinfunction "Y8_16") (pintype "tri_state"))
    )
    (net (code "79") (name "Net-(CONFD2-{slash}HDSEL)") (class "Default")
      (node (ref "CONFD2") (pin "32") (pinfunction "/HDSEL_32") (pintype "output"))
      (node (ref "IC9") (pin "23") (pinfunction "Y1_23") (pintype "tri_state"))
    )
    (net (code "80") (name "Net-(CONFD2-{slash}MOTENA)") (class "Default")
      (node (ref "CONFD2") (pin "10") (pinfunction "/MOTENA_10") (pintype "output"))
      (node (ref "IC9") (pin "15") (pinfunction "Y9_15") (pintype "tri_state"))
    )
    (net (code "81") (name "Net-(CONFD2-{slash}MOTENB)") (class "Default")
      (node (ref "CONFD2") (pin "16") (pinfunction "/MOTENB_16") (pintype "output"))
      (node (ref "IC9") (pin "18") (pinfunction "Y6_18") (pintype "tri_state"))
    )
    (net (code "82") (name "Net-(CONFD2-{slash}REDWRC)") (class "Default")
      (node (ref "CONFD2") (pin "2") (pinfunction "/REDWRC_2") (pintype "output"))
      (node (ref "IC9") (pin "14") (pinfunction "Y10_14") (pintype "tri_state"))
    )
    (net (code "83") (name "Net-(CONFD2-{slash}STEP)") (class "Default")
      (node (ref "CONFD2") (pin "20") (pinfunction "/STEP_20") (pintype "output"))
      (node (ref "IC9") (pin "20") (pinfunction "Y4_20") (pintype "tri_state"))
    )
    (net (code "84") (name "Net-(CONFD2-{slash}WDATA)") (class "Default")
      (node (ref "CONFD2") (pin "22") (pinfunction "/WDATA_22") (pintype "output"))
      (node (ref "IC9") (pin "21") (pinfunction "Y3_21") (pintype "tri_state"))
    )
    (net (code "85") (name "Net-(CONFD2-{slash}WGATE)") (class "Default")
      (node (ref "CONFD2") (pin "24") (pinfunction "/WGATE_24") (pintype "output"))
      (node (ref "IC9") (pin "22") (pinfunction "Y2_22") (pintype "tri_state"))
    )
    (net (code "86") (name "Net-(CONFD3-{slash}DIR)") (class "Default")
      (node (ref "CONFD3") (pin "18") (pinfunction "/DIR_18") (pintype "output"))
      (node (ref "IC10") (pin "19") (pinfunction "Y5_19") (pintype "tri_state"))
    )
    (net (code "87") (name "Net-(CONFD3-{slash}DRSELA)") (class "Default")
      (node (ref "CONFD3") (pin "14") (pinfunction "/DRSELA_14") (pintype "output"))
      (node (ref "IC10") (pin "17") (pinfunction "Y7_17") (pintype "tri_state"))
    )
    (net (code "88") (name "Net-(CONFD3-{slash}DRSELB)") (class "Default")
      (node (ref "CONFD3") (pin "12") (pinfunction "/DRSELB_12") (pintype "output"))
      (node (ref "IC10") (pin "16") (pinfunction "Y8_16") (pintype "tri_state"))
    )
    (net (code "89") (name "Net-(CONFD3-{slash}HDSEL)") (class "Default")
      (node (ref "CONFD3") (pin "32") (pinfunction "/HDSEL_32") (pintype "output"))
      (node (ref "IC10") (pin "23") (pinfunction "Y1_23") (pintype "tri_state"))
    )
    (net (code "90") (name "Net-(CONFD3-{slash}MOTENA)") (class "Default")
      (node (ref "CONFD3") (pin "10") (pinfunction "/MOTENA_10") (pintype "output"))
      (node (ref "IC10") (pin "15") (pinfunction "Y9_15") (pintype "tri_state"))
    )
    (net (code "91") (name "Net-(CONFD3-{slash}MOTENB)") (class "Default")
      (node (ref "CONFD3") (pin "16") (pinfunction "/MOTENB_16") (pintype "output"))
      (node (ref "IC10") (pin "18") (pinfunction "Y6_18") (pintype "tri_state"))
    )
    (net (code "92") (name "Net-(CONFD3-{slash}REDWRC)") (class "Default")
      (node (ref "CONFD3") (pin "2") (pinfunction "/REDWRC_2") (pintype "output"))
      (node (ref "IC10") (pin "14") (pinfunction "Y10_14") (pintype "tri_state"))
    )
    (net (code "93") (name "Net-(CONFD3-{slash}STEP)") (class "Default")
      (node (ref "CONFD3") (pin "20") (pinfunction "/STEP_20") (pintype "output"))
      (node (ref "IC10") (pin "20") (pinfunction "Y4_20") (pintype "tri_state"))
    )
    (net (code "94") (name "Net-(CONFD3-{slash}WDATA)") (class "Default")
      (node (ref "CONFD3") (pin "22") (pinfunction "/WDATA_22") (pintype "output"))
      (node (ref "IC10") (pin "21") (pinfunction "Y3_21") (pintype "tri_state"))
    )
    (net (code "95") (name "Net-(CONFD3-{slash}WGATE)") (class "Default")
      (node (ref "CONFD3") (pin "24") (pinfunction "/WGATE_24") (pintype "output"))
      (node (ref "IC10") (pin "22") (pinfunction "Y2_22") (pintype "tri_state"))
    )
    (net (code "96") (name "Net-(CONFD4-{slash}DIR)") (class "Default")
      (node (ref "CONFD4") (pin "18") (pinfunction "/DIR_18") (pintype "output"))
      (node (ref "IC11") (pin "19") (pinfunction "Y5_19") (pintype "tri_state"))
    )
    (net (code "97") (name "Net-(CONFD4-{slash}DRSELA)") (class "Default")
      (node (ref "CONFD4") (pin "14") (pinfunction "/DRSELA_14") (pintype "output"))
      (node (ref "IC11") (pin "17") (pinfunction "Y7_17") (pintype "tri_state"))
    )
    (net (code "98") (name "Net-(CONFD4-{slash}DRSELB)") (class "Default")
      (node (ref "CONFD4") (pin "12") (pinfunction "/DRSELB_12") (pintype "output"))
      (node (ref "IC11") (pin "16") (pinfunction "Y8_16") (pintype "tri_state"))
    )
    (net (code "99") (name "Net-(CONFD4-{slash}HDSEL)") (class "Default")
      (node (ref "CONFD4") (pin "32") (pinfunction "/HDSEL_32") (pintype "output"))
      (node (ref "IC11") (pin "23") (pinfunction "Y1_23") (pintype "tri_state"))
    )
    (net (code "100") (name "Net-(CONFD4-{slash}MOTENA)") (class "Default")
      (node (ref "CONFD4") (pin "10") (pinfunction "/MOTENA_10") (pintype "output"))
      (node (ref "IC11") (pin "15") (pinfunction "Y9_15") (pintype "tri_state"))
    )
    (net (code "101") (name "Net-(CONFD4-{slash}MOTENB)") (class "Default")
      (node (ref "CONFD4") (pin "16") (pinfunction "/MOTENB_16") (pintype "output"))
      (node (ref "IC11") (pin "18") (pinfunction "Y6_18") (pintype "tri_state"))
    )
    (net (code "102") (name "Net-(CONFD4-{slash}REDWRC)") (class "Default")
      (node (ref "CONFD4") (pin "2") (pinfunction "/REDWRC_2") (pintype "output"))
      (node (ref "IC11") (pin "14") (pinfunction "Y10_14") (pintype "tri_state"))
    )
    (net (code "103") (name "Net-(CONFD4-{slash}STEP)") (class "Default")
      (node (ref "CONFD4") (pin "20") (pinfunction "/STEP_20") (pintype "output"))
      (node (ref "IC11") (pin "20") (pinfunction "Y4_20") (pintype "tri_state"))
    )
    (net (code "104") (name "Net-(CONFD4-{slash}WDATA)") (class "Default")
      (node (ref "CONFD4") (pin "22") (pinfunction "/WDATA_22") (pintype "output"))
      (node (ref "IC11") (pin "21") (pinfunction "Y3_21") (pintype "tri_state"))
    )
    (net (code "105") (name "Net-(CONFD4-{slash}WGATE)") (class "Default")
      (node (ref "CONFD4") (pin "24") (pinfunction "/WGATE_24") (pintype "output"))
      (node (ref "IC11") (pin "22") (pinfunction "Y2_22") (pintype "tri_state"))
    )
    (net (code "106") (name "Net-(IC1A-1G)") (class "Default")
      (node (ref "IC1") (pin "1") (pinfunction "1G_1") (pintype "input"))
      (node (ref "IC2") (pin "1") (pinfunction "1G_1") (pintype "input"))
      (node (ref "IC3") (pin "1") (pinfunction "1G_1") (pintype "input"))
      (node (ref "IC5") (pin "13") (pinfunction "GBA_13") (pintype "input"))
      (node (ref "IC6") (pin "13") (pinfunction "G2_13") (pintype "input"))
      (node (ref "R1") (pin "2") (pinfunction "2_2") (pintype "passive"))
      (node (ref "SW2-1") (pin "1") (pinfunction "P_1") (pintype "passive"))
    )
    (net (code "107") (name "Net-(IC1A-2G)") (class "Default")
      (node (ref "IC1") (pin "15") (pinfunction "2G_15") (pintype "input"))
      (node (ref "IC2") (pin "15") (pinfunction "2G_15") (pintype "input"))
      (node (ref "IC3") (pin "15") (pinfunction "2G_15") (pintype "input"))
      (node (ref "IC4") (pin "13") (pinfunction "GBA_13") (pintype "input"))
      (node (ref "IC7") (pin "1") (pinfunction "G1_1") (pintype "input"))
      (node (ref "R2") (pin "2") (pinfunction "2_2") (pintype "passive"))
      (node (ref "SW2-2") (pin "1") (pinfunction "P_1") (pintype "passive"))
    )
    (net (code "108") (name "Net-(IC1A-A)") (class "Default")
      (node (ref "D2") (pin "A") (pinfunction "A_A") (pintype "passive"))
      (node (ref "D3") (pin "A") (pinfunction "A_A") (pintype "passive"))
      (node (ref "IC1") (pin "14") (pinfunction "A_14") (pintype "input"))
      (node (ref "IC2") (pin "14") (pinfunction "A_14") (pintype "input"))
      (node (ref "IC3") (pin "14") (pinfunction "A_14") (pintype "input"))
      (node (ref "R7") (pin "1") (pinfunction "1_1") (pintype "passive"))
    )
    (net (code "109") (name "Net-(IC1A-B)") (class "Default")
      (node (ref "D1") (pin "A") (pinfunction "A_A") (pintype "passive"))
      (node (ref "D4") (pin "A") (pinfunction "A_A") (pintype "passive"))
      (node (ref "IC1") (pin "2") (pinfunction "B_2") (pintype "input"))
      (node (ref "IC2") (pin "2") (pinfunction "B_2") (pintype "input"))
      (node (ref "IC3") (pin "2") (pinfunction "B_2") (pintype "input"))
      (node (ref "R8") (pin "1") (pinfunction "1_1") (pintype "passive"))
    )
    (net (code "110") (name "Net-(IC8A-G2)") (class "Default")
      (node (ref "D1") (pin "C") (pinfunction "C_C") (pintype "passive"))
      (node (ref "D2") (pin "C") (pinfunction "C_C") (pintype "passive"))
      (node (ref "IC8") (pin "13") (pinfunction "G2_13") (pintype "input"))
      (node (ref "R3") (pin "1") (pinfunction "1_1") (pintype "passive"))
      (node (ref "SW1-1") (pin "1") (pinfunction "P_1") (pintype "passive"))
    )
    (net (code "111") (name "Net-(IC9A-G1)") (class "Default")
      (node (ref "D3") (pin "C") (pinfunction "C_C") (pintype "passive"))
      (node (ref "IC9") (pin "1") (pinfunction "G1_1") (pintype "input"))
      (node (ref "R4") (pin "1") (pinfunction "1_1") (pintype "passive"))
      (node (ref "SW1-2") (pin "1") (pinfunction "P_1") (pintype "passive"))
    )
    (net (code "112") (name "Net-(IC10A-G2)") (class "Default")
      (node (ref "D4") (pin "C") (pinfunction "C_C") (pintype "passive"))
      (node (ref "IC10") (pin "13") (pinfunction "G2_13") (pintype "input"))
      (node (ref "R5") (pin "1") (pinfunction "1_1") (pintype "passive"))
      (node (ref "SW1-3") (pin "1") (pinfunction "P_1") (pintype "passive"))
    )
    (net (code "113") (name "Net-(IC11A-G1)") (class "Default")
      (node (ref "IC11") (pin "1") (pinfunction "G1_1") (pintype "input"))
      (node (ref "R6") (pin "1") (pinfunction "1_1") (pintype "passive"))
      (node (ref "SW1-4") (pin "1") (pinfunction "P_1") (pintype "passive"))
    )
    (net (code "114") (name "Net-(J1A-S)") (class "Default")
      (node (ref "J1") (pin "1") (pinfunction "S_1") (pintype "passive"))
      (node (ref "SJ1") (pin "1") (pinfunction "1_1") (pintype "passive"))
    )
    (net (code "115") (name "Net-(J1D-S)") (class "Default")
      (node (ref "J1") (pin "4") (pinfunction "S_4") (pintype "passive"))
      (node (ref "SJ1") (pin "3") (pinfunction "3_3") (pintype "passive"))
    )
    (net (code "116") (name "VCC") (class "Default")
      (node (ref "C1") (pin "1") (pinfunction "1_1") (pintype "passive"))
      (node (ref "C10") (pin "1") (pinfunction "1_1") (pintype "passive"))
      (node (ref "C11") (pin "1") (pinfunction "1_1") (pintype "passive"))
      (node (ref "C12") (pin "+") (pinfunction "+_+") (pintype "passive"))
      (node (ref "C2") (pin "1") (pinfunction "1_1") (pintype "passive"))
      (node (ref "C3") (pin "1") (pinfunction "1_1") (pintype "passive"))
      (node (ref "C4") (pin "1") (pinfunction "1_1") (pintype "passive"))
      (node (ref "C5") (pin "1") (pinfunction "1_1") (pintype "passive"))
      (node (ref "C6") (pin "1") (pinfunction "1_1") (pintype "passive"))
      (node (ref "C7") (pin "1") (pinfunction "1_1") (pintype "passive"))
      (node (ref "C8") (pin "1") (pinfunction "1_1") (pintype "passive"))
      (node (ref "C9") (pin "1") (pinfunction "1_1") (pintype "passive"))
      (node (ref "IC1") (pin "16") (pinfunction "VCC_16") (pintype "power_in"))
      (node (ref "IC10") (pin "24") (pinfunction "VCC_24") (pintype "power_in"))
      (node (ref "IC11") (pin "24") (pinfunction "VCC_24") (pintype "power_in"))
      (node (ref "IC2") (pin "16") (pinfunction "VCC_16") (pintype "power_in"))
      (node (ref "IC3") (pin "16") (pinfunction "VCC_16") (pintype "power_in"))
      (node (ref "IC4") (pin "1") (pinfunction "GAB_1") (pintype "input"))
      (node (ref "IC4") (pin "14") (pinfunction "VCC_14") (pintype "power_in"))
      (node (ref "IC5") (pin "1") (pinfunction "GAB_1") (pintype "input"))
      (node (ref "IC5") (pin "14") (pinfunction "VCC_14") (pintype "power_in"))
      (node (ref "IC6") (pin "24") (pinfunction "VCC_24") (pintype "power_in"))
      (node (ref "IC7") (pin "24") (pinfunction "VCC_24") (pintype "power_in"))
      (node (ref "IC8") (pin "24") (pinfunction "VCC_24") (pintype "power_in"))
      (node (ref "IC9") (pin "24") (pinfunction "VCC_24") (pintype "power_in"))
      (node (ref "R1") (pin "1") (pinfunction "1_1") (pintype "passive"))
      (node (ref "R2") (pin "1") (pinfunction "1_1") (pintype "passive"))
      (node (ref "R3") (pin "2") (pinfunction "2_2") (pintype "passive"))
      (node (ref "R4") (pin "2") (pinfunction "2_2") (pintype "passive"))
      (node (ref "R5") (pin "2") (pinfunction "2_2") (pintype "passive"))
      (node (ref "R6") (pin "2") (pinfunction "2_2") (pintype "passive"))
      (node (ref "R7") (pin "2") (pinfunction "2_2") (pintype "passive"))
      (node (ref "R8") (pin "2") (pinfunction "2_2") (pintype "passive"))
      (node (ref "SJ1") (pin "2") (pinfunction "2_2") (pintype "passive"))
    )
    (net (code "117") (name "unconnected-(CONFD1-NC-Pad4)") (class "Default")
      (node (ref "CONFD1") (pin "4") (pinfunction "NC_4") (pintype "no_connect"))
    )
    (net (code "118") (name "unconnected-(CONFD1-NC-Pad6)") (class "Default")
      (node (ref "CONFD1") (pin "6") (pinfunction "NC_6") (pintype "no_connect"))
    )
    (net (code "119") (name "unconnected-(CONFD2-NC-Pad4)") (class "Default")
      (node (ref "CONFD2") (pin "4") (pinfunction "NC_4") (pintype "no_connect"))
    )
    (net (code "120") (name "unconnected-(CONFD2-NC-Pad6)") (class "Default")
      (node (ref "CONFD2") (pin "6") (pinfunction "NC_6") (pintype "no_connect"))
    )
    (net (code "121") (name "unconnected-(CONFD3-NC-Pad4)") (class "Default")
      (node (ref "CONFD3") (pin "4") (pinfunction "NC_4") (pintype "no_connect"))
    )
    (net (code "122") (name "unconnected-(CONFD3-NC-Pad6)") (class "Default")
      (node (ref "CONFD3") (pin "6") (pinfunction "NC_6") (pintype "no_connect"))
    )
    (net (code "123") (name "unconnected-(CONFD4-NC-Pad4)") (class "Default")
      (node (ref "CONFD4") (pin "4") (pinfunction "NC_4") (pintype "no_connect"))
    )
    (net (code "124") (name "unconnected-(CONFD4-NC-Pad6)") (class "Default")
      (node (ref "CONFD4") (pin "6") (pinfunction "NC_6") (pintype "no_connect"))
    )
    (net (code "125") (name "unconnected-(CON_CRYO-NC-Pad4)") (class "Default")
      (node (ref "CON_CRYO") (pin "4") (pinfunction "NC_4") (pintype "no_connect"))
    )
    (net (code "126") (name "unconnected-(CON_CRYO-NC-Pad6)") (class "Default")
      (node (ref "CON_CRYO") (pin "6") (pinfunction "NC_6") (pintype "no_connect"))
    )
    (net (code "127") (name "unconnected-(CON_FDC-NC-Pad4)") (class "Default")
      (node (ref "CON_FDC") (pin "4") (pinfunction "NC_4") (pintype "no_connect"))
    )
    (net (code "128") (name "unconnected-(CON_FDC-NC-Pad6)") (class "Default")
      (node (ref "CON_FDC") (pin "6") (pinfunction "NC_6") (pintype "no_connect"))
    )
  )
)
